# design.net
KiCad netlist of a schematic drawn in Altium Designer
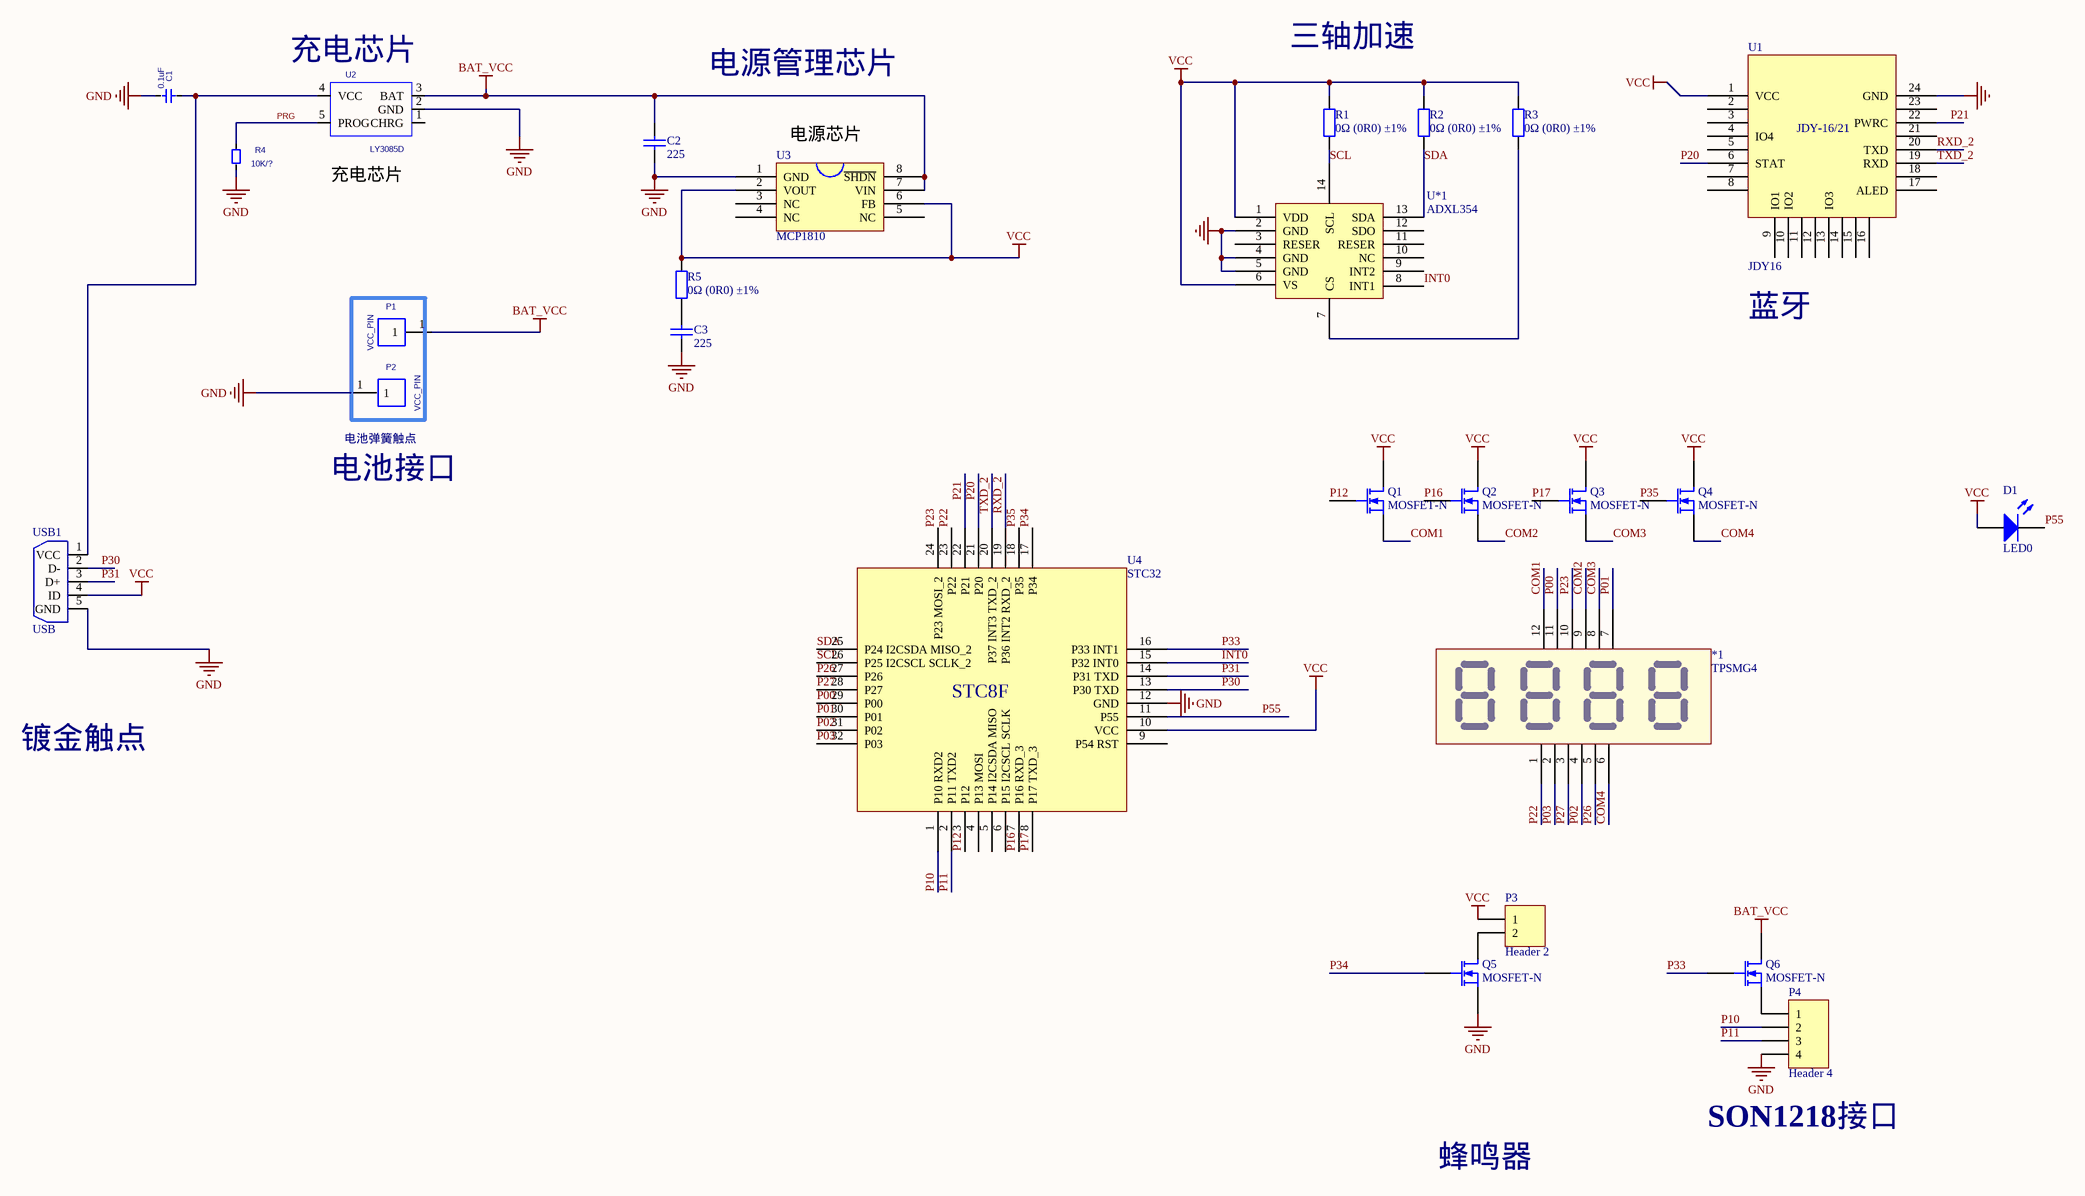
[diagram p0: 手环.SchDoc]

(export (version "E")
  (design (tool "Eeschema 10.0.6"))
  (components
    (comp (ref "*1") (value "TPSMG4") (footprint "TPSMG4") (libsource (lib "stc64") (part "TPSMG4")))
    (comp (ref "C1")
      (value "0.1uF")
      (footprint "0603LED1")
      (description "0.1uF-0402")
      (libsource (lib "*") (part "C"))
    )
    (comp (ref "C2")
      (value "225")
      (footprint "0603LED1")
      (description "1206贴片电容")
      (libsource (lib "02 Miscellaneous_Devices_ZSF_Library") (part "Cap_1206"))
    )
    (comp (ref "C3")
      (value "225")
      (footprint "0603LED1")
      (description "1206贴片电容")
      (libsource (lib "02 Miscellaneous_Devices_ZSF_Library") (part "Cap_1206"))
    )
    (comp (ref "D1")
      (value "LED0")
      (footprint "0603LED1")
      (description "Typical INFRARED GaAs LED")
      (fields (field (name "PUBLISHER") "Altium Limited"))
      (libsource (lib "Miscellaneous Devices") (part "LED0"))
    )
    (comp (ref "P1") (value "VCC_PIN") (footprint "SMDCD") (libsource (lib "*") (part "VCC_PIN")))
    (comp (ref "P2") (value "VCC_PIN") (footprint "SMDCD") (libsource (lib "*") (part "VCC_PIN")))
    (comp (ref "P3")
      (value "Header 2")
      (footprint "DET402")
      (description "Header, 2-Pin")
      (fields (field (name "PUBLISHER") "Altium Limited"))
      (libsource (lib "01 Connect_IntegratedLibrary") (part "Header 2"))
    )
    (comp (ref "P4")
      (value "Header 4")
      (footprint "FPC4")
      (description "Header, 4-Pin")
      (fields (field (name "PUBLISHER") "Altium Limited"))
      (libsource (lib "Miscellaneous Connectors") (part "Header 4"))
    )
    (comp (ref "Q1")
      (value "MOSFET-N")
      (footprint "TPMOS")
      (description "N-Channel MOSFET")
      (fields (field (name "PUBLISHER") "Altium Limited"))
      (libsource (lib "Miscellaneous Devices") (part "MOSFET-N"))
    )
    (comp (ref "Q2")
      (value "MOSFET-N")
      (footprint "TPMOS")
      (description "N-Channel MOSFET")
      (fields (field (name "PUBLISHER") "Altium Limited"))
      (libsource (lib "Miscellaneous Devices") (part "MOSFET-N"))
    )
    (comp (ref "Q3")
      (value "MOSFET-N")
      (footprint "TPMOS")
      (description "N-Channel MOSFET")
      (fields (field (name "PUBLISHER") "Altium Limited"))
      (libsource (lib "Miscellaneous Devices") (part "MOSFET-N"))
    )
    (comp (ref "Q4")
      (value "MOSFET-N")
      (footprint "TPMOS")
      (description "N-Channel MOSFET")
      (fields (field (name "PUBLISHER") "Altium Limited"))
      (libsource (lib "Miscellaneous Devices") (part "MOSFET-N"))
    )
    (comp (ref "Q5")
      (value "MOSFET-N")
      (footprint "TPMOS")
      (description "N-Channel MOSFET")
      (fields (field (name "PUBLISHER") "Altium Limited"))
      (libsource (lib "Miscellaneous Devices") (part "MOSFET-N"))
    )
    (comp (ref "Q6")
      (value "MOSFET-N")
      (footprint "TPMOS")
      (description "N-Channel MOSFET")
      (fields (field (name "PUBLISHER") "Altium Limited"))
      (libsource (lib "Miscellaneous Devices") (part "MOSFET-N"))
    )
    (comp (ref "R1")
      (value "0Ω (0R0) ±1%")
      (footprint "0603LED1")
      (description "贴片电阻")
      (libsource (lib "02 Miscellaneous_Devices_ZSF_Library") (part "Res_0603"))
    )
    (comp (ref "R2")
      (value "0Ω (0R0) ±1%")
      (footprint "0603LED1")
      (description "贴片电阻")
      (libsource (lib "02 Miscellaneous_Devices_ZSF_Library") (part "Res_0603"))
    )
    (comp (ref "R3")
      (value "0Ω (0R0) ±1%")
      (footprint "0603LED1")
      (description "贴片电阻")
      (libsource (lib "02 Miscellaneous_Devices_ZSF_Library") (part "Res_0603"))
    )
    (comp (ref "R4")
      (value "10K/?")
      (footprint "0603LED1")
      (description "10K-0402 1%")
      (libsource (lib "*") (part "RSET"))
    )
    (comp (ref "R5")
      (value "0Ω (0R0) ±1%")
      (footprint "0603LED1")
      (description "贴片电阻")
      (libsource (lib "") (part "Res_0603_1"))
    )
    (comp (ref "U*1") (value "ADXL354") (footprint "ADXL345") (libsource (lib "stc64") (part "ADXL354")))
    (comp (ref "U1") (value "JDY16") (footprint "JDY16") (libsource (lib "stc64") (part "JDY21")))
    (comp (ref "U2")
      (value "LY3085D")
      (footprint "SOT-23-5")
      (libsource (lib "*") (part "TP4055-42-SOT25-R"))
    )
    (comp (ref "U3") (value "MCP1810") (footprint "J8A") (libsource (lib "LDO") (part "MCP1810")))
    (comp (ref "U4") (value "STC32") (footprint "QFN32") (libsource (lib "stc64") (part "STC32")))
    (comp (ref "USB1")
      (value "USB")
      (footprint "MICRO-USB-插脚-卷边")
      (libsource (lib "01 Connect_IntegratedLibrary") (part "USB5"))
    )
  )
  (nets
    (net (code "1") (name "/COM1") (class "Default")
      (node (ref "*1") (pin "12") (pinfunction "12_12") (pintype "passive"))
      (node (ref "Q1") (pin "3") (pinfunction "S_3") (pintype "passive"))
    )
    (net (code "2") (name "/COM2") (class "Default")
      (node (ref "*1") (pin "9") (pinfunction "9_9") (pintype "passive"))
      (node (ref "Q2") (pin "3") (pinfunction "S_3") (pintype "passive"))
    )
    (net (code "3") (name "/COM3") (class "Default")
      (node (ref "*1") (pin "8") (pinfunction "8_8") (pintype "passive"))
      (node (ref "Q3") (pin "3") (pinfunction "S_3") (pintype "passive"))
    )
    (net (code "4") (name "/COM4") (class "Default")
      (node (ref "*1") (pin "6") (pinfunction "6_6") (pintype "passive"))
      (node (ref "Q4") (pin "3") (pinfunction "S_3") (pintype "passive"))
    )
    (net (code "5") (name "/INT0") (class "Default")
      (node (ref "U*1") (pin "8") (pinfunction "INT1_8") (pintype "passive"))
      (node (ref "U4") (pin "15") (pinfunction "P32_INT0_15") (pintype "passive"))
    )
    (net (code "6") (name "/P00") (class "Default")
      (node (ref "*1") (pin "11") (pinfunction "11_11") (pintype "passive"))
      (node (ref "U4") (pin "29") (pinfunction "P00_29") (pintype "passive"))
    )
    (net (code "7") (name "/P01") (class "Default")
      (node (ref "*1") (pin "7") (pinfunction "7_7") (pintype "passive"))
      (node (ref "U4") (pin "30") (pinfunction "P01_30") (pintype "passive"))
    )
    (net (code "8") (name "/P02") (class "Default")
      (node (ref "*1") (pin "4") (pinfunction "4_4") (pintype "passive"))
      (node (ref "U4") (pin "31") (pinfunction "P02_31") (pintype "passive"))
    )
    (net (code "9") (name "/P03") (class "Default")
      (node (ref "*1") (pin "2") (pinfunction "2_2") (pintype "passive"))
      (node (ref "U4") (pin "32") (pinfunction "P03_32") (pintype "passive"))
    )
    (net (code "10") (name "/P10") (class "Default")
      (node (ref "P4") (pin "2") (pinfunction "2_2") (pintype "passive"))
      (node (ref "U4") (pin "1") (pinfunction "P10_RXD2_1") (pintype "passive"))
    )
    (net (code "11") (name "/P11") (class "Default")
      (node (ref "P4") (pin "3") (pinfunction "3_3") (pintype "passive"))
      (node (ref "U4") (pin "2") (pinfunction "P11_TXD2_2") (pintype "passive"))
    )
    (net (code "12") (name "/P12") (class "Default")
      (node (ref "Q1") (pin "2") (pinfunction "G_2") (pintype "passive"))
      (node (ref "U4") (pin "3") (pinfunction "P12_3") (pintype "passive"))
    )
    (net (code "13") (name "/P16") (class "Default")
      (node (ref "Q2") (pin "2") (pinfunction "G_2") (pintype "passive"))
      (node (ref "U4") (pin "7") (pinfunction "P16_RXD_3_7") (pintype "passive"))
    )
    (net (code "14") (name "/P17") (class "Default")
      (node (ref "Q3") (pin "2") (pinfunction "G_2") (pintype "passive"))
      (node (ref "U4") (pin "8") (pinfunction "P17_TXD_3_8") (pintype "passive"))
    )
    (net (code "15") (name "/P20") (class "Default")
      (node (ref "U1") (pin "6") (pinfunction "STAT_6") (pintype "passive"))
      (node (ref "U4") (pin "21") (pinfunction "P20_21") (pintype "passive"))
    )
    (net (code "16") (name "/P21") (class "Default")
      (node (ref "U1") (pin "22") (pinfunction "PWRC_22") (pintype "passive"))
      (node (ref "U4") (pin "22") (pinfunction "P21_22") (pintype "passive"))
    )
    (net (code "17") (name "/P22") (class "Default")
      (node (ref "*1") (pin "1") (pinfunction "1_1") (pintype "passive"))
      (node (ref "U4") (pin "23") (pinfunction "P22_23") (pintype "passive"))
    )
    (net (code "18") (name "/P23") (class "Default")
      (node (ref "*1") (pin "10") (pinfunction "10_10") (pintype "passive"))
      (node (ref "U4") (pin "24") (pinfunction "P23_MOSI_2_24") (pintype "passive"))
    )
    (net (code "19") (name "/P26") (class "Default")
      (node (ref "*1") (pin "5") (pinfunction "5_5") (pintype "passive"))
      (node (ref "U4") (pin "27") (pinfunction "P26_27") (pintype "passive"))
    )
    (net (code "20") (name "/P27") (class "Default")
      (node (ref "*1") (pin "3") (pinfunction "3_3") (pintype "passive"))
      (node (ref "U4") (pin "28") (pinfunction "P27_28") (pintype "passive"))
    )
    (net (code "21") (name "/P30") (class "Default")
      (node (ref "U4") (pin "13") (pinfunction "P30_TXD_13") (pintype "passive"))
      (node (ref "USB1") (pin "2") (pinfunction "D-_2") (pintype "passive"))
    )
    (net (code "22") (name "/P31") (class "Default")
      (node (ref "U4") (pin "14") (pinfunction "P31_TXD_14") (pintype "passive"))
      (node (ref "USB1") (pin "3") (pinfunction "D+_3") (pintype "passive"))
    )
    (net (code "23") (name "/P33") (class "Default")
      (node (ref "Q6") (pin "2") (pinfunction "G_2") (pintype "passive"))
      (node (ref "U4") (pin "16") (pinfunction "P33_INT1_16") (pintype "passive"))
    )
    (net (code "24") (name "/P34") (class "Default")
      (node (ref "Q5") (pin "2") (pinfunction "G_2") (pintype "passive"))
      (node (ref "U4") (pin "17") (pinfunction "P34_17") (pintype "passive"))
    )
    (net (code "25") (name "/P35") (class "Default")
      (node (ref "Q4") (pin "2") (pinfunction "G_2") (pintype "passive"))
      (node (ref "U4") (pin "18") (pinfunction "P35_18") (pintype "passive"))
    )
    (net (code "26") (name "/P55") (class "Default")
      (node (ref "D1") (pin "2") (pinfunction "K_2") (pintype "passive"))
      (node (ref "U4") (pin "11") (pinfunction "P55_11") (pintype "passive"))
    )
    (net (code "27") (name "/PRG") (class "Default")
      (node (ref "R4") (pin "2") (pinfunction "2_2") (pintype "passive"))
      (node (ref "U2") (pin "5") (pinfunction "PROG_5") (pintype "passive"))
    )
    (net (code "28") (name "/RXD_2") (class "Default")
      (node (ref "U1") (pin "20") (pinfunction "TXD_20") (pintype "passive"))
      (node (ref "U4") (pin "19") (pinfunction "P36_INT2_RXD_2_19") (pintype "passive"))
    )
    (net (code "29") (name "/SCL") (class "Default")
      (node (ref "R1") (pin "2") (pinfunction "2_2") (pintype "passive"))
      (node (ref "U*1") (pin "14") (pinfunction "SCL_14") (pintype "passive"))
      (node (ref "U4") (pin "26") (pinfunction "P25_I2CSCL_SCLK_2_26") (pintype "passive"))
    )
    (net (code "30") (name "/SDA") (class "Default")
      (node (ref "R2") (pin "2") (pinfunction "2_2") (pintype "passive"))
      (node (ref "U*1") (pin "13") (pinfunction "SDA_13") (pintype "passive"))
      (node (ref "U4") (pin "25") (pinfunction "P24_I2CSDA_MISO_2_25") (pintype "passive"))
    )
    (net (code "31") (name "/TXD_2") (class "Default")
      (node (ref "U1") (pin "19") (pinfunction "RXD_19") (pintype "passive"))
      (node (ref "U4") (pin "20") (pinfunction "P37_INT3_TXD_2_20") (pintype "passive"))
    )
    (net (code "32") (name "BAT_VCC") (class "Default")
      (node (ref "C2") (pin "1") (pinfunction "1_1") (pintype "passive"))
      (node (ref "P1") (pin "1") (pinfunction "1_1") (pintype "passive"))
      (node (ref "Q6") (pin "1") (pinfunction "D_1") (pintype "passive"))
      (node (ref "U2") (pin "3") (pinfunction "BAT_3") (pintype "passive"))
      (node (ref "U3") (pin "7") (pinfunction "VIN_7") (pintype "passive"))
      (node (ref "U3") (pin "8") (pinfunction "~{SHDN}_8") (pintype "passive"))
    )
    (net (code "33") (name "GND") (class "Default")
      (node (ref "C1") (pin "2") (pinfunction "2_2") (pintype "passive"))
      (node (ref "C2") (pin "2") (pinfunction "2_2") (pintype "passive"))
      (node (ref "C3") (pin "2") (pinfunction "2_2") (pintype "passive"))
      (node (ref "P2") (pin "1") (pinfunction "1_1") (pintype "passive"))
      (node (ref "P4") (pin "4") (pinfunction "4_4") (pintype "passive"))
      (node (ref "Q5") (pin "3") (pinfunction "S_3") (pintype "passive"))
      (node (ref "R4") (pin "1") (pinfunction "1_1") (pintype "passive"))
      (node (ref "U*1") (pin "2") (pinfunction "GND_2") (pintype "passive"))
      (node (ref "U*1") (pin "4") (pinfunction "GND_4") (pintype "passive"))
      (node (ref "U*1") (pin "5") (pinfunction "GND_5") (pintype "passive"))
      (node (ref "U1") (pin "24") (pinfunction "GND_24") (pintype "passive"))
      (node (ref "U2") (pin "2") (pinfunction "GND_2") (pintype "passive"))
      (node (ref "U3") (pin "1") (pinfunction "GND_1") (pintype "passive"))
      (node (ref "U4") (pin "12") (pinfunction "GND_12") (pintype "passive"))
      (node (ref "USB1") (pin "5") (pinfunction "GND_5") (pintype "passive"))
    )
    (net (code "34") (name "Net-(C3-Pad1)") (class "Default")
      (node (ref "C3") (pin "1") (pinfunction "1_1") (pintype "passive"))
      (node (ref "R5") (pin "1") (pinfunction "1_1") (pintype "passive"))
    )
    (net (code "35") (name "Net-(Q5-D)") (class "Default")
      (node (ref "P3") (pin "2") (pinfunction "2_2") (pintype "passive"))
      (node (ref "Q5") (pin "1") (pinfunction "D_1") (pintype "passive"))
    )
    (net (code "36") (name "Net-(Q6-S)") (class "Default")
      (node (ref "P4") (pin "1") (pinfunction "1_1") (pintype "passive"))
      (node (ref "Q6") (pin "3") (pinfunction "S_3") (pintype "passive"))
    )
    (net (code "37") (name "Net-(U*1-CS)") (class "Default")
      (node (ref "R3") (pin "2") (pinfunction "2_2") (pintype "passive"))
      (node (ref "U*1") (pin "7") (pinfunction "CS_7") (pintype "passive"))
    )
    (net (code "38") (name "Net-(U2-VCC)") (class "Default")
      (node (ref "C1") (pin "1") (pinfunction "1_1") (pintype "passive"))
      (node (ref "U2") (pin "4") (pinfunction "VCC_4") (pintype "passive"))
      (node (ref "USB1") (pin "1") (pinfunction "VCC_1") (pintype "passive"))
    )
    (net (code "39") (name "VCC") (class "Default")
      (node (ref "D1") (pin "1") (pinfunction "A_1") (pintype "passive"))
      (node (ref "P3") (pin "1") (pinfunction "1_1") (pintype "passive"))
      (node (ref "Q1") (pin "1") (pinfunction "D_1") (pintype "passive"))
      (node (ref "Q2") (pin "1") (pinfunction "D_1") (pintype "passive"))
      (node (ref "Q3") (pin "1") (pinfunction "D_1") (pintype "passive"))
      (node (ref "Q4") (pin "1") (pinfunction "D_1") (pintype "passive"))
      (node (ref "R1") (pin "1") (pinfunction "1_1") (pintype "passive"))
      (node (ref "R2") (pin "1") (pinfunction "1_1") (pintype "passive"))
      (node (ref "R3") (pin "1") (pinfunction "1_1") (pintype "passive"))
      (node (ref "R5") (pin "2") (pinfunction "2_2") (pintype "passive"))
      (node (ref "U*1") (pin "1") (pinfunction "VDD_1") (pintype "passive"))
      (node (ref "U*1") (pin "6") (pinfunction "VS_6") (pintype "passive"))
      (node (ref "U1") (pin "1") (pinfunction "VCC_1") (pintype "passive"))
      (node (ref "U3") (pin "2") (pinfunction "VOUT_2") (pintype "passive"))
      (node (ref "U3") (pin "6") (pinfunction "FB_6") (pintype "passive"))
      (node (ref "U4") (pin "10") (pinfunction "VCC_10") (pintype "passive"))
      (node (ref "USB1") (pin "4") (pinfunction "ID_4") (pintype "passive"))
    )
    (net (code "40") (name "unconnected-(U*1-INT2-Pad9)") (class "Default")
      (node (ref "U*1") (pin "9") (pinfunction "INT2_9") (pintype "passive"))
    )
    (net (code "41") (name "unconnected-(U*1-NC-Pad10)") (class "Default")
      (node (ref "U*1") (pin "10") (pinfunction "NC_10") (pintype "passive"))
    )
    (net (code "42") (name "unconnected-(U*1-RESER-Pad3)") (class "Default")
      (node (ref "U*1") (pin "3") (pinfunction "RESER_3") (pintype "passive"))
    )
    (net (code "43") (name "unconnected-(U*1-RESER-Pad11)") (class "Default")
      (node (ref "U*1") (pin "11") (pinfunction "RESER_11") (pintype "passive"))
    )
    (net (code "44") (name "unconnected-(U*1-SDO-Pad12)") (class "Default")
      (node (ref "U*1") (pin "12") (pinfunction "SDO_12") (pintype "passive"))
    )
    (net (code "45") (name "unconnected-(U1-ALED-Pad17)") (class "Default")
      (node (ref "U1") (pin "17") (pinfunction "ALED_17") (pintype "passive"))
    )
    (net (code "46") (name "unconnected-(U1-IO1-Pad9)") (class "Default")
      (node (ref "U1") (pin "9") (pinfunction "IO1_9") (pintype "passive"))
    )
    (net (code "47") (name "unconnected-(U1-IO2-Pad10)") (class "Default")
      (node (ref "U1") (pin "10") (pinfunction "IO2_10") (pintype "passive"))
    )
    (net (code "48") (name "unconnected-(U1-IO3-Pad13)") (class "Default")
      (node (ref "U1") (pin "13") (pinfunction "IO3_13") (pintype "passive"))
    )
    (net (code "49") (name "unconnected-(U1-IO4-Pad4)") (class "Default")
      (node (ref "U1") (pin "4") (pinfunction "IO4_4") (pintype "passive"))
    )
    (net (code "50") (name "unconnected-(U1-Pad2)") (class "Default")
      (node (ref "U1") (pin "2") (pintype "passive"))
    )
    (net (code "51") (name "unconnected-(U1-Pad3)") (class "Default")
      (node (ref "U1") (pin "3") (pintype "passive"))
    )
    (net (code "52") (name "unconnected-(U1-Pad5)") (class "Default")
      (node (ref "U1") (pin "5") (pintype "passive"))
    )
    (net (code "53") (name "unconnected-(U1-Pad7)") (class "Default")
      (node (ref "U1") (pin "7") (pintype "passive"))
    )
    (net (code "54") (name "unconnected-(U1-Pad8)") (class "Default")
      (node (ref "U1") (pin "8") (pintype "passive"))
    )
    (net (code "55") (name "unconnected-(U1-Pad11)") (class "Default")
      (node (ref "U1") (pin "11") (pintype "passive"))
    )
    (net (code "56") (name "unconnected-(U1-Pad12)") (class "Default")
      (node (ref "U1") (pin "12") (pintype "passive"))
    )
    (net (code "57") (name "unconnected-(U1-Pad14)") (class "Default")
      (node (ref "U1") (pin "14") (pintype "passive"))
    )
    (net (code "58") (name "unconnected-(U1-Pad15)") (class "Default")
      (node (ref "U1") (pin "15") (pintype "passive"))
    )
    (net (code "59") (name "unconnected-(U1-Pad16)") (class "Default")
      (node (ref "U1") (pin "16") (pintype "passive"))
    )
    (net (code "60") (name "unconnected-(U1-Pad18)") (class "Default")
      (node (ref "U1") (pin "18") (pintype "passive"))
    )
    (net (code "61") (name "unconnected-(U1-Pad21)") (class "Default")
      (node (ref "U1") (pin "21") (pintype "passive"))
    )
    (net (code "62") (name "unconnected-(U1-Pad23)") (class "Default")
      (node (ref "U1") (pin "23") (pintype "passive"))
    )
    (net (code "63") (name "unconnected-(U2-CHRG-Pad1)") (class "Default")
      (node (ref "U2") (pin "1") (pinfunction "CHRG_1") (pintype "passive"))
    )
    (net (code "64") (name "unconnected-(U3-NC-Pad3)") (class "Default")
      (node (ref "U3") (pin "3") (pinfunction "NC_3") (pintype "passive"))
    )
    (net (code "65") (name "unconnected-(U3-NC-Pad4)") (class "Default")
      (node (ref "U3") (pin "4") (pinfunction "NC_4") (pintype "passive"))
    )
    (net (code "66") (name "unconnected-(U3-NC-Pad5)") (class "Default")
      (node (ref "U3") (pin "5") (pinfunction "NC_5") (pintype "passive"))
    )
    (net (code "67") (name "unconnected-(U4-P13_MOSI-Pad4)") (class "Default")
      (node (ref "U4") (pin "4") (pinfunction "P13_MOSI_4") (pintype "passive"))
    )
    (net (code "68") (name "unconnected-(U4-P14_I2CSDA_MISO-Pad5)") (class "Default")
      (node (ref "U4") (pin "5") (pinfunction "P14_I2CSDA_MISO_5") (pintype "passive"))
    )
    (net (code "69") (name "unconnected-(U4-P15_I2CSCL_SCLK-Pad6)") (class "Default")
      (node (ref "U4") (pin "6") (pinfunction "P15_I2CSCL_SCLK_6") (pintype "passive"))
    )
    (net (code "70") (name "unconnected-(U4-P54_RST-Pad9)") (class "Default")
      (node (ref "U4") (pin "9") (pinfunction "P54_RST_9") (pintype "passive"))
    )
  )
)
